# RFM2Pi_v2_7_1.net
KiCad netlist of a schematic drawn in EAGLE
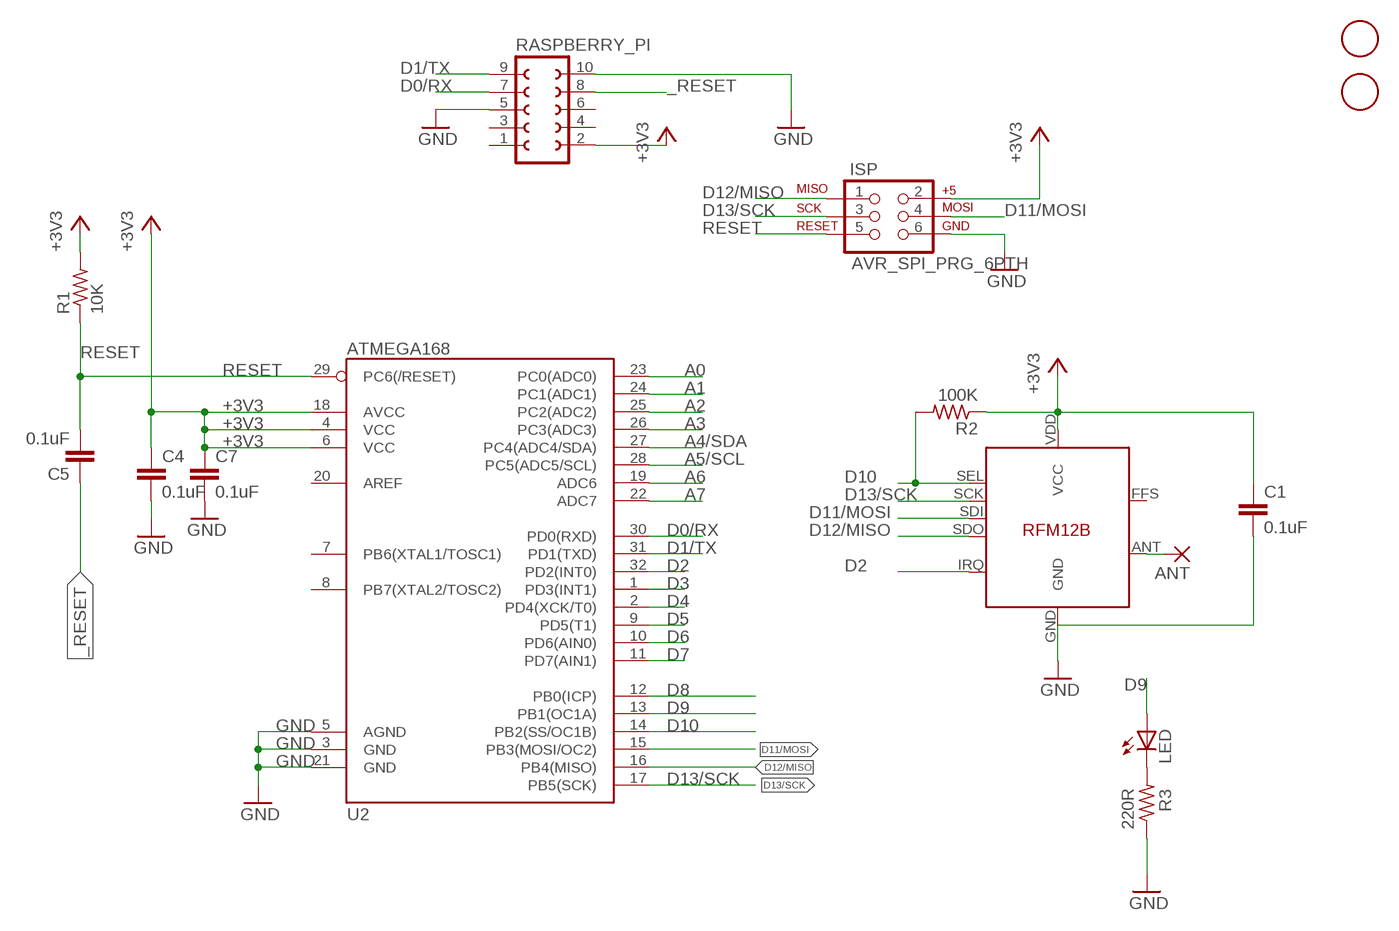
[diagram p0: schematic, sheet 1]

(export (version "E")
  (design (tool "Eeschema 10.0.6"))
  (components
    (comp (ref "ANT")
      (value "1,6/0,8")
      (footprint "eagle-import:1,6_0,8")
      (libsource (lib "eagle-import") (part "1,6/0,8"))
    )
    (comp (ref "C1")
      (value "0.1uF")
      (footprint "eagle-import:C0603")
      (libsource (lib "eagle-import") (part "C-EUC0603"))
    )
    (comp (ref "C4")
      (value "0.1uF")
      (footprint "eagle-import:C0603")
      (libsource (lib "eagle-import") (part "C-EUC0603"))
    )
    (comp (ref "C5")
      (value "0.1uF")
      (footprint "eagle-import:C0603")
      (libsource (lib "eagle-import") (part "C-EUC0603"))
    )
    (comp (ref "C7")
      (value "0.1uF")
      (footprint "eagle-import:C0603")
      (libsource (lib "eagle-import") (part "resistor_C-EUC0603"))
    )
    (comp (ref "ISP")
      (value "AVR_SPI_PRG_6PTH")
      (footprint "eagle-import:2X3")
      (libsource (lib "eagle-import") (part "AVR_SPI_PRG_6PTH"))
    )
    (comp (ref "LED")
      (value "LEDSML0603")
      (footprint "eagle-import:SML0603")
      (libsource (lib "eagle-import") (part "LEDSML0603"))
    )
    (comp (ref "R1")
      (value "10K")
      (footprint "eagle-import:R0603")
      (libsource (lib "eagle-import") (part "R-US_R0603"))
    )
    (comp (ref "R2")
      (value "100K")
      (footprint "eagle-import:R0603")
      (libsource (lib "eagle-import") (part "R-US_R0603"))
    )
    (comp (ref "R3")
      (value "220R")
      (footprint "eagle-import:R0603")
      (libsource (lib "eagle-import") (part "R-US_R0603"))
    )
    (comp (ref "RASPBERRY_PI")
      (value "FE05-2")
      (footprint "eagle-import:FE05-2")
      (libsource (lib "eagle-import") (part "FE05-2"))
    )
    (comp (ref "RFM12B")
      (value "RFM12B")
      (footprint "eagle-import:RFM12B")
      (libsource (lib "eagle-import") (part "RFM12B"))
    )
    (comp (ref "U$1")
      (value "FIDUCIAL")
      (footprint "eagle-import:FIDUCIAL_1MM")
      (libsource (lib "eagle-import") (part "FIDUCIAL"))
    )
    (comp (ref "U$2")
      (value "FIDUCIAL")
      (footprint "eagle-import:FIDUCIAL_1MM")
      (libsource (lib "eagle-import") (part "FIDUCIAL"))
    )
    (comp (ref "U2")
      (value "ATMEGA168")
      (footprint "eagle-import:TQFP32-08")
      (libsource (lib "eagle-import") (part "ATMEGA168"))
    )
  )
  (nets
    (net (code "1") (name "+3V3") (class "Default")
      (node (ref "C1") (pin "1") (pinfunction "1_1") (pintype "passive"))
      (node (ref "C4") (pin "1") (pinfunction "1_1") (pintype "passive"))
      (node (ref "C7") (pin "1") (pinfunction "1_1") (pintype "passive"))
      (node (ref "ISP") (pin "2") (pinfunction "2_2") (pintype "passive"))
      (node (ref "R1") (pin "2") (pinfunction "2_2") (pintype "passive"))
      (node (ref "R2") (pin "1") (pinfunction "1_1") (pintype "passive"))
      (node (ref "RASPBERRY_PI") (pin "2") (pinfunction "2_2") (pintype "passive"))
      (node (ref "RFM12B") (pin "VDD") (pinfunction "VCC_VDD") (pintype "power_in"))
      (node (ref "U2") (pin "18") (pinfunction "AVCC_18") (pintype "bidirectional"))
      (node (ref "U2") (pin "4") (pinfunction "VCC_4") (pintype "bidirectional"))
      (node (ref "U2") (pin "6") (pinfunction "VCC_6") (pintype "bidirectional"))
    )
    (net (code "2") (name "/A0") (class "Default")
      (node (ref "U2") (pin "23") (pinfunction "PC0(ADC0)_23") (pintype "bidirectional"))
    )
    (net (code "3") (name "/A1") (class "Default")
      (node (ref "U2") (pin "24") (pinfunction "PC1(ADC1)_24") (pintype "bidirectional"))
    )
    (net (code "4") (name "/A2") (class "Default")
      (node (ref "U2") (pin "25") (pinfunction "PC2(ADC2)_25") (pintype "bidirectional"))
    )
    (net (code "5") (name "/A3") (class "Default")
      (node (ref "U2") (pin "26") (pinfunction "PC3(ADC3)_26") (pintype "bidirectional"))
    )
    (net (code "6") (name "/A4{slash}SDA") (class "Default")
      (node (ref "U2") (pin "27") (pinfunction "PC4(ADC4/SDA)_27") (pintype "bidirectional"))
    )
    (net (code "7") (name "/A5{slash}SCL") (class "Default")
      (node (ref "U2") (pin "28") (pinfunction "PC5(ADC5/SCL)_28") (pintype "bidirectional"))
    )
    (net (code "8") (name "/A6") (class "Default")
      (node (ref "U2") (pin "19") (pinfunction "ADC6_19") (pintype "bidirectional"))
    )
    (net (code "9") (name "/A7") (class "Default")
      (node (ref "U2") (pin "22") (pinfunction "ADC7_22") (pintype "bidirectional"))
    )
    (net (code "10") (name "/D0{slash}RX") (class "Default")
      (node (ref "RASPBERRY_PI") (pin "7") (pinfunction "7_7") (pintype "passive"))
      (node (ref "U2") (pin "30") (pinfunction "PD0(RXD)_30") (pintype "bidirectional"))
    )
    (net (code "11") (name "/D1{slash}TX") (class "Default")
      (node (ref "RASPBERRY_PI") (pin "9") (pinfunction "9_9") (pintype "passive"))
      (node (ref "U2") (pin "31") (pinfunction "PD1(TXD)_31") (pintype "bidirectional"))
    )
    (net (code "12") (name "/D2") (class "Default")
      (node (ref "RFM12B") (pin "IRQ") (pinfunction "IRQ_IRQ") (pintype "open_collector"))
      (node (ref "U2") (pin "32") (pinfunction "PD2(INT0)_32") (pintype "bidirectional"))
    )
    (net (code "13") (name "/D3") (class "Default")
      (node (ref "U2") (pin "1") (pinfunction "PD3(INT1)_1") (pintype "bidirectional"))
    )
    (net (code "14") (name "/D4") (class "Default")
      (node (ref "U2") (pin "2") (pinfunction "PD4(XCK/T0)_2") (pintype "bidirectional"))
    )
    (net (code "15") (name "/D5") (class "Default")
      (node (ref "U2") (pin "9") (pinfunction "PD5(T1)_9") (pintype "bidirectional"))
    )
    (net (code "16") (name "/D6") (class "Default")
      (node (ref "U2") (pin "10") (pinfunction "PD6(AIN0)_10") (pintype "bidirectional"))
    )
    (net (code "17") (name "/D7") (class "Default")
      (node (ref "U2") (pin "11") (pinfunction "PD7(AIN1)_11") (pintype "bidirectional"))
    )
    (net (code "18") (name "/D8") (class "Default")
      (node (ref "U2") (pin "12") (pinfunction "PB0(ICP)_12") (pintype "bidirectional"))
    )
    (net (code "19") (name "/D9") (class "Default")
      (node (ref "LED") (pin "A") (pinfunction "A_A") (pintype "passive"))
      (node (ref "U2") (pin "13") (pinfunction "PB1(OC1A)_13") (pintype "bidirectional"))
    )
    (net (code "20") (name "/D10") (class "Default")
      (node (ref "R2") (pin "2") (pinfunction "2_2") (pintype "passive"))
      (node (ref "RFM12B") (pin "SEL") (pinfunction "SEL_SEL") (pintype "input"))
      (node (ref "U2") (pin "14") (pinfunction "PB2(SS/OC1B)_14") (pintype "bidirectional"))
    )
    (net (code "21") (name "/RESET") (class "Default")
      (node (ref "C5") (pin "2") (pinfunction "2_2") (pintype "passive"))
      (node (ref "ISP") (pin "5") (pinfunction "5_5") (pintype "passive"))
      (node (ref "R1") (pin "1") (pinfunction "1_1") (pintype "passive"))
      (node (ref "U2") (pin "29") (pinfunction "PC6(/RESET)_29") (pintype "bidirectional"))
    )
    (net (code "22") (name "D11{slash}MOSI") (class "Default")
      (node (ref "ISP") (pin "4") (pinfunction "4_4") (pintype "passive"))
      (node (ref "RFM12B") (pin "SDI") (pinfunction "SDI_SDI") (pintype "input"))
      (node (ref "U2") (pin "15") (pinfunction "PB3(MOSI/OC2)_15") (pintype "bidirectional"))
    )
    (net (code "23") (name "D12{slash}MISO") (class "Default")
      (node (ref "ISP") (pin "1") (pinfunction "1_1") (pintype "passive"))
      (node (ref "RFM12B") (pin "SDO") (pinfunction "SDO_SDO") (pintype "output"))
      (node (ref "U2") (pin "16") (pinfunction "PB4(MISO)_16") (pintype "bidirectional"))
    )
    (net (code "24") (name "D13{slash}SCK") (class "Default")
      (node (ref "ISP") (pin "3") (pinfunction "3_3") (pintype "passive"))
      (node (ref "RFM12B") (pin "SCK") (pinfunction "SCK_SCK") (pintype "input"))
      (node (ref "U2") (pin "17") (pinfunction "PB5(SCK)_17") (pintype "bidirectional"))
    )
    (net (code "25") (name "GND") (class "Default")
      (node (ref "C1") (pin "2") (pinfunction "2_2") (pintype "passive"))
      (node (ref "C4") (pin "2") (pinfunction "2_2") (pintype "passive"))
      (node (ref "C7") (pin "2") (pinfunction "2_2") (pintype "passive"))
      (node (ref "ISP") (pin "6") (pinfunction "6_6") (pintype "passive"))
      (node (ref "R3") (pin "1") (pinfunction "1_1") (pintype "passive"))
      (node (ref "RASPBERRY_PI") (pin "10") (pinfunction "10_10") (pintype "passive"))
      (node (ref "RASPBERRY_PI") (pin "5") (pinfunction "5_5") (pintype "passive"))
      (node (ref "RFM12B") (pin "GND") (pinfunction "GND_GND") (pintype "power_in"))
      (node (ref "U2") (pin "21") (pinfunction "GND_21") (pintype "bidirectional"))
      (node (ref "U2") (pin "3") (pinfunction "GND_3") (pintype "bidirectional"))
      (node (ref "U2") (pin "5") (pinfunction "AGND_5") (pintype "bidirectional"))
    )
    (net (code "26") (name "Net-(ANT-P)") (class "Default")
      (node (ref "ANT") (pin "1") (pinfunction "P_1") (pintype "passive"))
      (node (ref "RFM12B") (pin "ANT") (pinfunction "ANT_ANT") (pintype "passive"))
    )
    (net (code "27") (name "Net-(LED-PadC)") (class "Default")
      (node (ref "LED") (pin "C") (pinfunction "C_C") (pintype "passive"))
      (node (ref "R3") (pin "2") (pinfunction "2_2") (pintype "passive"))
    )
    (net (code "28") (name "_RESET") (class "Default")
      (node (ref "C5") (pin "1") (pinfunction "1_1") (pintype "passive"))
      (node (ref "RASPBERRY_PI") (pin "8") (pinfunction "8_8") (pintype "passive"))
    )
    (net (code "29") (name "unconnected-(RASPBERRY_PI-Pad1)") (class "Default")
      (node (ref "RASPBERRY_PI") (pin "1") (pinfunction "1_1") (pintype "passive"))
    )
    (net (code "30") (name "unconnected-(RASPBERRY_PI-Pad3)") (class "Default")
      (node (ref "RASPBERRY_PI") (pin "3") (pinfunction "3_3") (pintype "passive"))
    )
    (net (code "31") (name "unconnected-(RASPBERRY_PI-Pad4)") (class "Default")
      (node (ref "RASPBERRY_PI") (pin "4") (pinfunction "4_4") (pintype "passive"))
    )
    (net (code "32") (name "unconnected-(RASPBERRY_PI-Pad6)") (class "Default")
      (node (ref "RASPBERRY_PI") (pin "6") (pinfunction "6_6") (pintype "passive"))
    )
    (net (code "33") (name "unconnected-(RFM12B-PadFFS)") (class "Default")
      (node (ref "RFM12B") (pin "FFS") (pinfunction "FFS_FFS") (pintype "bidirectional"))
    )
    (net (code "34") (name "unconnected-(U2-AREF-Pad20)") (class "Default")
      (node (ref "U2") (pin "20") (pinfunction "AREF_20") (pintype "bidirectional"))
    )
    (net (code "35") (name "unconnected-(U2-PB6(XTAL1{slash}TOSC1)-Pad7)") (class "Default")
      (node (ref "U2") (pin "7") (pinfunction "PB6(XTAL1/TOSC1)_7") (pintype "bidirectional"))
    )
    (net (code "36") (name "unconnected-(U2-PB7(XTAL2{slash}TOSC2)-Pad8)") (class "Default")
      (node (ref "U2") (pin "8") (pinfunction "PB7(XTAL2/TOSC2)_8") (pintype "bidirectional"))
    )
  )
)
